# 5_StepperMotorDriver.net
KiCad netlist of a schematic drawn in Altium Designer
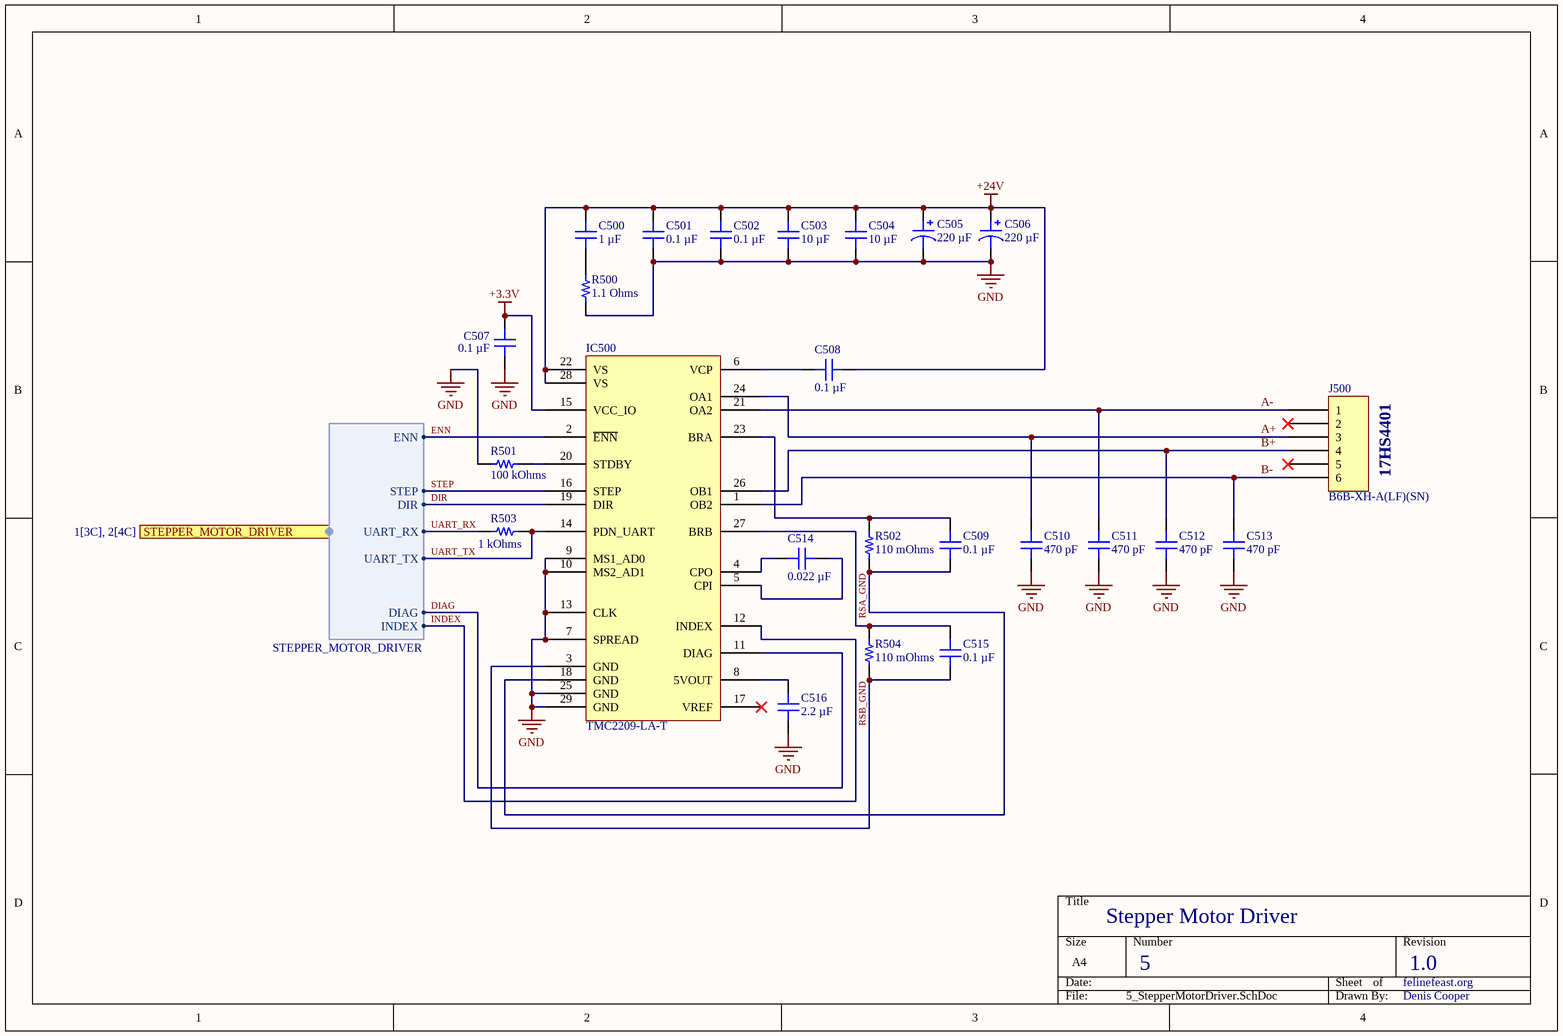
[diagram p0: 5_StepperMotorDriver.SchDoc]

(export (version "E")
  (design (tool "Eeschema 10.0.6"))
  (components
    (comp (ref "C500")
      (value "1 µF")
      (footprint "CAP 1210_3225 - 1MM")
      (description "CAP CER 1UF 50V X7R 1210")
      (fields
        (field (name "PART NUMBER") "CL32B105KBHNNNE")
        (field (name "MANUFACTURER") "Samsung Electro-Mechanics")
      )
      (libsource (lib "Celestial Altium Library - altium_library") (part "Capacitor"))
    )
    (comp (ref "C501")
      (value "0.1 µF")
      (footprint "CAP 0603_1608")
      (description "CAP CER 0.1UF 50V X7R 0603")
      (fields
        (field (name "PART NUMBER") "CL10B104KB8NNNC")
        (field (name "CAPACITANCE") "0.1 µF")
        (field (name "MANUFACTURER") "Samsung Electro-Mechanics")
      )
      (libsource (lib "Celestial Altium Library - altium_library") (part "Capacitor"))
    )
    (comp (ref "C502")
      (value "0.1 µF")
      (footprint "CAP 0603_1608")
      (description "CAP CER 0.1UF 50V X7R 0603")
      (fields
        (field (name "PART NUMBER") "CL10B104KB8NNNC")
        (field (name "CAPACITANCE") "0.1 µF")
        (field (name "MANUFACTURER") "Samsung Electro-Mechanics")
      )
      (libsource (lib "Celestial Altium Library - altium_library") (part "Capacitor"))
    )
    (comp (ref "C503")
      (value "10 µF")
      (footprint "CAP 1206_3216 - 0.8MM")
      (description "CAP CER 10UF 50V X7R 1206")
      (fields
        (field (name "PART NUMBER") "CL31B106KBHNNNE")
        (field (name "CAPACITANCE") "10 µF")
        (field (name "MANUFACTURER") "Samsung Electro-Mechanics")
      )
      (libsource (lib "Celestial Altium Library - altium_library") (part "Capacitor"))
    )
    (comp (ref "C504")
      (value "10 µF")
      (footprint "CAP 1206_3216 - 0.8MM")
      (description "CAP CER 10UF 50V X7R 1206")
      (fields
        (field (name "PART NUMBER") "CL31B106KBHNNNE")
        (field (name "CAPACITANCE") "10 µF")
        (field (name "MANUFACTURER") "Samsung Electro-Mechanics")
      )
      (libsource (lib "Celestial Altium Library - altium_library") (part "Capacitor"))
    )
    (comp (ref "C505")
      (value "220 µF")
      (footprint "CAP ALSMD 8.3MM H10.5MM")
      (description "CAP ALUM 220UF 20% 50V SMD")
      (fields
        (field (name "PART NUMBER") "EEE-FT1H221GP")
        (field (name "MANUFACTURER") "Panasonic Electronic Components")
      )
      (libsource (lib "Celestial Altium Library - altium_library") (part "Polarised Capacitor"))
    )
    (comp (ref "C506")
      (value "220 µF")
      (footprint "CAP ALSMD 8.3MM H10.5MM")
      (description "CAP ALUM 220UF 20% 50V SMD")
      (fields
        (field (name "PART NUMBER") "EEE-FT1H221GP")
        (field (name "MANUFACTURER") "Panasonic Electronic Components")
      )
      (libsource (lib "Celestial Altium Library - altium_library") (part "Polarised Capacitor"))
    )
    (comp (ref "C507")
      (value "0.1 µF")
      (footprint "CAP 0603_1608")
      (description "CAP CER 0.1UF 50V X7R 0603")
      (fields
        (field (name "PART NUMBER") "CL10B104KB8NNNC")
        (field (name "CAPACITANCE") "0.1 µF")
        (field (name "MANUFACTURER") "Samsung Electro-Mechanics")
      )
      (libsource (lib "Celestial Altium Library - altium_library") (part "Capacitor"))
    )
    (comp (ref "C508")
      (value "0.1 µF")
      (footprint "CAP 0603_1608")
      (description "CAP CER 0.1UF 50V X7R 0603")
      (fields
        (field (name "PART NUMBER") "CL10B104KB8NNNC")
        (field (name "CAPACITANCE") "0.1 µF")
        (field (name "MANUFACTURER") "Samsung Electro-Mechanics")
      )
      (libsource (lib "Celestial Altium Library - altium_library") (part "Capacitor"))
    )
    (comp (ref "C509")
      (value "0.1 µF")
      (footprint "CAP 0603_1608")
      (description "CAP CER 0.1UF 50V X7R 0603")
      (fields
        (field (name "PART NUMBER") "CL10B104KB8NNNC")
        (field (name "CAPACITANCE") "0.1 µF")
        (field (name "MANUFACTURER") "Samsung Electro-Mechanics")
      )
      (libsource (lib "Celestial Altium Library - altium_library") (part "Capacitor"))
    )
    (comp (ref "C510")
      (value "470 pF")
      (footprint "CAP 0603_1608")
      (description "CAP CER 470PF 50V C0G/NP0 0603")
      (fields
        (field (name "PART NUMBER") "CL10C471JB8NNNC")
        (field (name "CAPACITANCE") "470 pF")
        (field (name "MANUFACTURER") "Samsung Electro-Mechanics")
      )
      (libsource (lib "Celestial Altium Library - altium_library") (part "Capacitor"))
    )
    (comp (ref "C511")
      (value "470 pF")
      (footprint "CAP 0603_1608")
      (description "CAP CER 470PF 50V C0G/NP0 0603")
      (fields
        (field (name "PART NUMBER") "CL10C471JB8NNNC")
        (field (name "CAPACITANCE") "470 pF")
        (field (name "MANUFACTURER") "Samsung Electro-Mechanics")
      )
      (libsource (lib "Celestial Altium Library - altium_library") (part "Capacitor"))
    )
    (comp (ref "C512")
      (value "470 pF")
      (footprint "CAP 0603_1608")
      (description "CAP CER 470PF 50V C0G/NP0 0603")
      (fields
        (field (name "PART NUMBER") "CL10C471JB8NNNC")
        (field (name "CAPACITANCE") "470 pF")
        (field (name "MANUFACTURER") "Samsung Electro-Mechanics")
      )
      (libsource (lib "Celestial Altium Library - altium_library") (part "Capacitor"))
    )
    (comp (ref "C513")
      (value "470 pF")
      (footprint "CAP 0603_1608")
      (description "CAP CER 470PF 50V C0G/NP0 0603")
      (fields
        (field (name "PART NUMBER") "CL10C471JB8NNNC")
        (field (name "CAPACITANCE") "470 pF")
        (field (name "MANUFACTURER") "Samsung Electro-Mechanics")
      )
      (libsource (lib "Celestial Altium Library - altium_library") (part "Capacitor"))
    )
    (comp (ref "C514")
      (value "0.022 µF")
      (footprint "CAP 0603_1608")
      (description "CAP CER 0.022UF 50V X7R 0603")
      (fields
        (field (name "PART NUMBER") "CL10B223KB8NNNC")
        (field (name "CAPACITANCE") "0.022 µF")
        (field (name "MANUFACTURER") "Samsung Electro-Mechanics")
      )
      (libsource (lib "Celestial Altium Library - altium_library") (part "Capacitor"))
    )
    (comp (ref "C515")
      (value "0.1 µF")
      (footprint "CAP 0603_1608")
      (description "CAP CER 0.1UF 50V X7R 0603")
      (fields
        (field (name "PART NUMBER") "CL10B104KB8NNNC")
        (field (name "CAPACITANCE") "0.1 µF")
        (field (name "MANUFACTURER") "Samsung Electro-Mechanics")
      )
      (libsource (lib "Celestial Altium Library - altium_library") (part "Capacitor"))
    )
    (comp (ref "C516")
      (value "2.2 µF")
      (footprint "CAP 0603_1608")
      (description "CAP CER 2.2UF 6.3V X5R 0603")
      (fields
        (field (name "PART NUMBER") "CL10A225KQ8NNNC")
        (field (name "CAPACITANCE") "2.2 µF")
        (field (name "MANUFACTURER") "Samsung Electro-Mechanics")
      )
      (libsource (lib "Celestial Altium Library - altium_library") (part "Capacitor"))
    )
    (comp (ref "IC500")
      (value "TMC2209-LA-T")
      (footprint "TRINAMIC QFN28 TMC2209-LA")
      (description "IC MTR DRV 4.75-28V QFN28")
      (fields (field (name "MANUFACTURER") "Trinamic Motion Control GmbH"))
      (libsource (lib "Celestial Altium Library - altium_library") (part "TRINAMIC TMC2209"))
    )
    (comp (ref "J500")
      (value "B6B-XH-A(LF)(SN)")
      (footprint "JST XH B6B-XH-A")
      (description "CONN HEADER VERT 6POS 2.5MM")
      (fields (field (name "MANUFACTURER") "JST Sales America Inc."))
      (libsource (lib "Celestial Altium Library - altium_library") (part "6 Pin"))
    )
    (comp (ref "R500")
      (value "1.1 Ohms")
      (footprint "YAGEO RES 0603_1608")
      (description "RES 1.1 OHM 1% 1/10W 0603")
      (fields (field (name "PART NUMBER") "RC0603FR-071R1L") (field (name "MANUFACTURER") "Yageo"))
      (libsource (lib "Celestial Altium Library - altium_library") (part "Resistor"))
    )
    (comp (ref "R501")
      (value "100 kOhms")
      (footprint "RES 0603_1608")
      (description "RES SMD 100K OHM 1% 1/10W 0603")
      (fields
        (field (name "PART NUMBER") "ERJ-3EKF1003V")
        (field (name "MANUFACTURER") "Panasonic Electronic Components")
      )
      (libsource (lib "Celestial Altium Library - altium_library") (part "Resistor"))
    )
    (comp (ref "R502")
      (value "110 mOhms")
      (footprint "RES 1210_3225")
      (description "RES 0.11 OHM 1% 1/2W 1210")
      (fields (field (name "PART NUMBER") "RL1210FR-070R11L") (field (name "MANUFACTURER") "Yageo"))
      (libsource (lib "Celestial Altium Library - altium_library") (part "Resistor"))
    )
    (comp (ref "R503")
      (value "1 kOhms")
      (footprint "RES 0603_1608")
      (description "RES SMD 1K OHM 1% 1/10W 0603")
      (fields
        (field (name "PART NUMBER") "ERJ-3EKF1001V")
        (field (name "MANUFACTURER") "Panasonic Electronic Components")
      )
      (libsource (lib "Celestial Altium Library - altium_library") (part "Resistor"))
    )
    (comp (ref "R504")
      (value "110 mOhms")
      (footprint "RES 1210_3225")
      (description "RES 0.11 OHM 1% 1/2W 1210")
      (fields (field (name "PART NUMBER") "RL1210FR-070R11L") (field (name "MANUFACTURER") "Yageo"))
      (libsource (lib "Celestial Altium Library - altium_library") (part "Resistor"))
    )
  )
  (nets
    (net (code "2") (name "+3.3V") (class "Default")
      (node (ref "C507") (pin "2") (pinfunction "2_2") (pintype "passive"))
      (node (ref "IC500") (pin "15") (pinfunction "VCC_IO_15") (pintype "passive"))
    )
    (net (code "3") (name "+24V") (class "Default")
      (node (ref "C500") (pin "2") (pinfunction "2_2") (pintype "passive"))
      (node (ref "C501") (pin "2") (pinfunction "2_2") (pintype "passive"))
      (node (ref "C502") (pin "2") (pinfunction "2_2") (pintype "passive"))
      (node (ref "C503") (pin "2") (pinfunction "2_2") (pintype "passive"))
      (node (ref "C504") (pin "2") (pinfunction "2_2") (pintype "passive"))
      (node (ref "C505") (pin "1") (pinfunction "1_1") (pintype "passive"))
      (node (ref "C506") (pin "1") (pinfunction "1_1") (pintype "passive"))
      (node (ref "C508") (pin "1") (pinfunction "1_1") (pintype "passive"))
      (node (ref "IC500") (pin "22") (pinfunction "VS_22") (pintype "passive"))
      (node (ref "IC500") (pin "28") (pinfunction "VS_28") (pintype "passive"))
    )
    (net (code "4") (name "/A+") (class "Default")
      (node (ref "C510") (pin "2") (pinfunction "2_2") (pintype "passive"))
      (node (ref "IC500") (pin "24") (pinfunction "OA1_24") (pintype "passive"))
      (node (ref "J500") (pin "3") (pinfunction "3_3") (pintype "passive"))
    )
    (net (code "5") (name "/A-") (class "Default")
      (node (ref "C511") (pin "2") (pinfunction "2_2") (pintype "passive"))
      (node (ref "IC500") (pin "21") (pinfunction "OA2_21") (pintype "passive"))
      (node (ref "J500") (pin "1") (pinfunction "1_1") (pintype "passive"))
    )
    (net (code "6") (name "/B+") (class "Default")
      (node (ref "C512") (pin "2") (pinfunction "2_2") (pintype "passive"))
      (node (ref "IC500") (pin "26") (pinfunction "OB1_26") (pintype "passive"))
      (node (ref "J500") (pin "4") (pinfunction "4_4") (pintype "passive"))
    )
    (net (code "7") (name "/B-") (class "Default")
      (node (ref "C513") (pin "2") (pinfunction "2_2") (pintype "passive"))
      (node (ref "IC500") (pin "1") (pinfunction "OB2_1") (pintype "passive"))
      (node (ref "J500") (pin "6") (pinfunction "6_6") (pintype "passive"))
    )
    (net (code "8") (name "/DIAG") (class "Default")
      (node (ref "IC500") (pin "11") (pinfunction "DIAG_11") (pintype "passive"))
    )
    (net (code "9") (name "/DIR") (class "Default")
      (node (ref "IC500") (pin "19") (pinfunction "DIR_19") (pintype "passive"))
    )
    (net (code "10") (name "/ENN") (class "Default")
      (node (ref "IC500") (pin "2") (pinfunction "~{ENN}_2") (pintype "passive"))
    )
    (net (code "11") (name "/INDEX") (class "Default")
      (node (ref "IC500") (pin "12") (pinfunction "INDEX_12") (pintype "passive"))
    )
    (net (code "12") (name "/RSA_GND") (class "Default")
      (node (ref "C509") (pin "2") (pinfunction "2_2") (pintype "passive"))
      (node (ref "IC500") (pin "18") (pinfunction "GND_18") (pintype "passive"))
      (node (ref "R502") (pin "1") (pinfunction "1_1") (pintype "passive"))
    )
    (net (code "13") (name "/RSB_GND") (class "Default")
      (node (ref "C515") (pin "2") (pinfunction "2_2") (pintype "passive"))
      (node (ref "IC500") (pin "3") (pinfunction "GND_3") (pintype "passive"))
      (node (ref "R504") (pin "1") (pinfunction "1_1") (pintype "passive"))
    )
    (net (code "14") (name "/STEP") (class "Default")
      (node (ref "IC500") (pin "16") (pinfunction "STEP_16") (pintype "passive"))
    )
    (net (code "15") (name "/UART_RX") (class "Default")
      (node (ref "R503") (pin "1") (pinfunction "1_1") (pintype "passive"))
    )
    (net (code "16") (name "/UART_TX") (class "Default")
      (node (ref "IC500") (pin "14") (pinfunction "PDN_UART_14") (pintype "passive"))
      (node (ref "R503") (pin "2") (pinfunction "2_2") (pintype "passive"))
    )
    (net (code "18") (name "GND") (class "Default")
      (node (ref "C501") (pin "1") (pinfunction "1_1") (pintype "passive"))
      (node (ref "C502") (pin "1") (pinfunction "1_1") (pintype "passive"))
      (node (ref "C503") (pin "1") (pinfunction "1_1") (pintype "passive"))
      (node (ref "C504") (pin "1") (pinfunction "1_1") (pintype "passive"))
      (node (ref "C505") (pin "2") (pinfunction "2_2") (pintype "passive"))
      (node (ref "C506") (pin "2") (pinfunction "2_2") (pintype "passive"))
      (node (ref "C507") (pin "1") (pinfunction "1_1") (pintype "passive"))
      (node (ref "C510") (pin "1") (pinfunction "1_1") (pintype "passive"))
      (node (ref "C511") (pin "1") (pinfunction "1_1") (pintype "passive"))
      (node (ref "C512") (pin "1") (pinfunction "1_1") (pintype "passive"))
      (node (ref "C513") (pin "1") (pinfunction "1_1") (pintype "passive"))
      (node (ref "C516") (pin "1") (pinfunction "1_1") (pintype "passive"))
      (node (ref "IC500") (pin "10") (pinfunction "MS2_AD1_10") (pintype "passive"))
      (node (ref "IC500") (pin "13") (pinfunction "CLK_13") (pintype "passive"))
      (node (ref "IC500") (pin "25") (pinfunction "GND_25") (pintype "passive"))
      (node (ref "IC500") (pin "29") (pinfunction "GND_29") (pintype "passive"))
      (node (ref "IC500") (pin "7") (pinfunction "SPREAD_7") (pintype "passive"))
      (node (ref "IC500") (pin "9") (pinfunction "MS1_AD0_9") (pintype "passive"))
      (node (ref "R500") (pin "1") (pinfunction "1_1") (pintype "passive"))
      (node (ref "R501") (pin "2") (pinfunction "2_2") (pintype "passive"))
    )
    (net (code "19") (name "Net-(C500-Pad1)") (class "Default")
      (node (ref "C500") (pin "1") (pinfunction "1_1") (pintype "passive"))
      (node (ref "R500") (pin "2") (pinfunction "2_2") (pintype "passive"))
    )
    (net (code "20") (name "Net-(IC500-5VOUT)") (class "Default")
      (node (ref "C516") (pin "2") (pinfunction "2_2") (pintype "passive"))
      (node (ref "IC500") (pin "8") (pinfunction "5VOUT_8") (pintype "passive"))
    )
    (net (code "21") (name "Net-(IC500-BRA)") (class "Default")
      (node (ref "C509") (pin "1") (pinfunction "1_1") (pintype "passive"))
      (node (ref "IC500") (pin "23") (pinfunction "BRA_23") (pintype "passive"))
      (node (ref "R502") (pin "2") (pinfunction "2_2") (pintype "passive"))
    )
    (net (code "22") (name "Net-(IC500-BRB)") (class "Default")
      (node (ref "C515") (pin "1") (pinfunction "1_1") (pintype "passive"))
      (node (ref "IC500") (pin "27") (pinfunction "BRB_27") (pintype "passive"))
      (node (ref "R504") (pin "2") (pinfunction "2_2") (pintype "passive"))
    )
    (net (code "23") (name "Net-(IC500-CPI)") (class "Default")
      (node (ref "C514") (pin "2") (pinfunction "2_2") (pintype "passive"))
      (node (ref "IC500") (pin "5") (pinfunction "CPI_5") (pintype "passive"))
    )
    (net (code "24") (name "Net-(IC500-CPO)") (class "Default")
      (node (ref "C514") (pin "1") (pinfunction "1_1") (pintype "passive"))
      (node (ref "IC500") (pin "4") (pinfunction "CPO_4") (pintype "passive"))
    )
    (net (code "25") (name "Net-(IC500-STDBY)") (class "Default")
      (node (ref "IC500") (pin "20") (pinfunction "STDBY_20") (pintype "passive"))
      (node (ref "R501") (pin "1") (pinfunction "1_1") (pintype "passive"))
    )
    (net (code "26") (name "Net-(IC500-VCP)") (class "Default")
      (node (ref "C508") (pin "2") (pinfunction "2_2") (pintype "passive"))
      (node (ref "IC500") (pin "6") (pinfunction "VCP_6") (pintype "passive"))
    )
    (net (code "27") (name "unconnected-(IC500-VREF-Pad17)") (class "Default")
      (node (ref "IC500") (pin "17") (pinfunction "VREF_17") (pintype "passive+no_connect"))
    )
    (net (code "28") (name "unconnected-(J500-Pad2)") (class "Default")
      (node (ref "J500") (pin "2") (pinfunction "2_2") (pintype "passive+no_connect"))
    )
    (net (code "29") (name "unconnected-(J500-Pad5)") (class "Default")
      (node (ref "J500") (pin "5") (pinfunction "5_5") (pintype "passive+no_connect"))
    )
  )
)
